# clock_divider.net
KiCad netlist of a schematic drawn in EAGLE
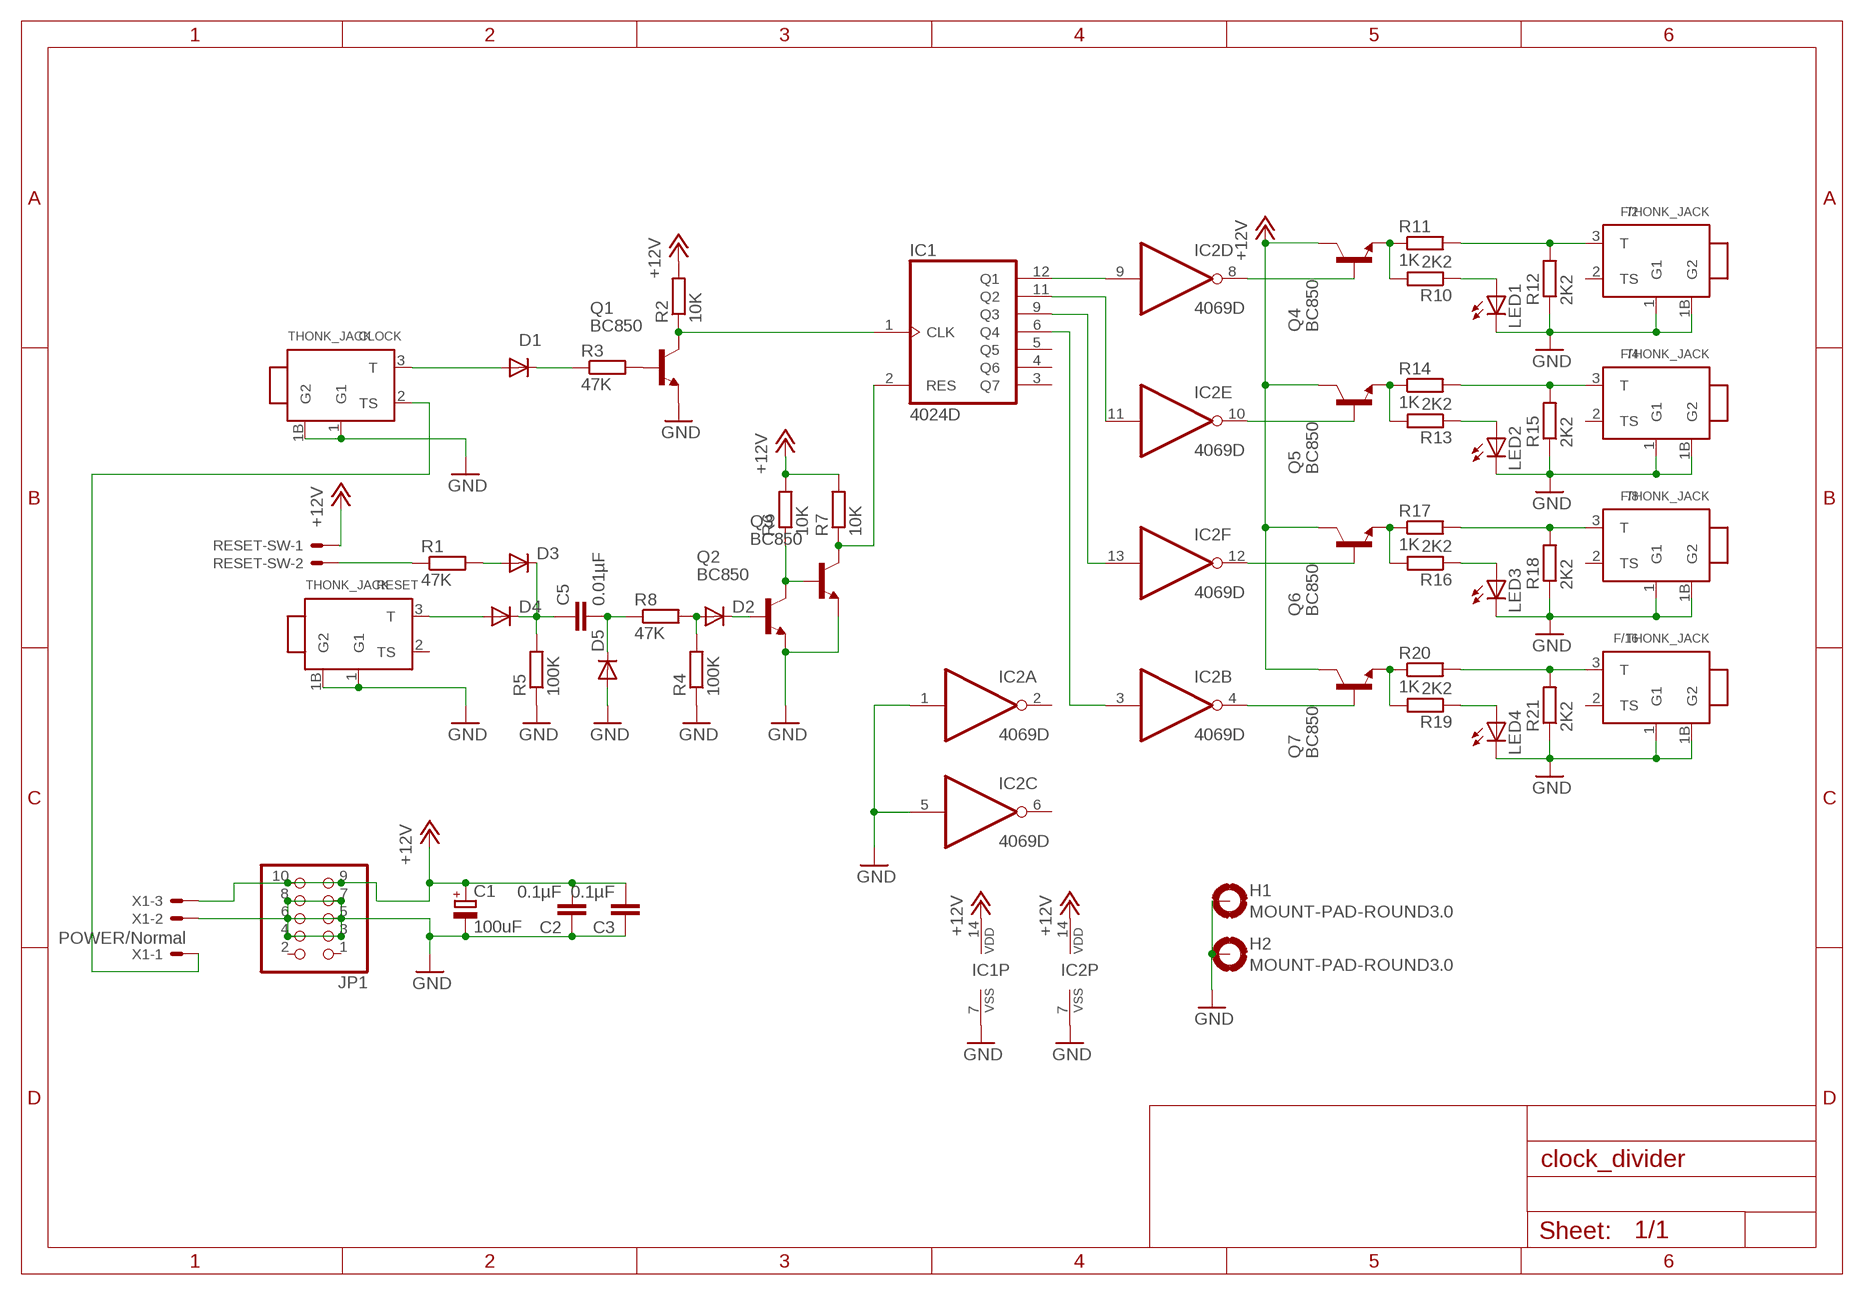
[diagram p0: schematic, sheet 1]

(export (version "E")
  (design (tool "Eeschema 10.0.6"))
  (components
    (comp (ref "C1")
      (value "100uF")
      (footprint "eagle-import:E2,5-6E")
      (libsource (lib "eagle-import") (part "CPOL-EUE2,5-6E"))
    )
    (comp (ref "C2")
      (value "0.1µF")
      (footprint "eagle-import:C0805")
      (libsource (lib "eagle-import") (part "C-EUC0805"))
    )
    (comp (ref "C3")
      (value "0.1µF")
      (footprint "eagle-import:C0805")
      (libsource (lib "eagle-import") (part "C-EUC0805"))
    )
    (comp (ref "C5")
      (value "0.01µF")
      (footprint "eagle-import:C0805")
      (libsource (lib "eagle-import") (part "C-EUC0805"))
    )
    (comp (ref "CLOCK")
      (value "THONK_JACK")
      (footprint "eagle-import:THONK_JACK_P")
      (libsource (lib "eagle-import") (part "THONK_JACK"))
    )
    (comp (ref "D1")
      (value "1N4148")
      (footprint "eagle-import:DO35-7")
      (libsource (lib "eagle-import") (part "1N4148DO35-7"))
    )
    (comp (ref "D2")
      (value "1N4148")
      (footprint "eagle-import:DO35-7")
      (libsource (lib "eagle-import") (part "1N4148DO35-7"))
    )
    (comp (ref "D3")
      (value "1N4148")
      (footprint "eagle-import:DO35-7")
      (libsource (lib "eagle-import") (part "1N4148DO35-7"))
    )
    (comp (ref "D4")
      (value "1N4148")
      (footprint "eagle-import:DO35-7")
      (libsource (lib "eagle-import") (part "1N4148DO35-7"))
    )
    (comp (ref "D5")
      (value "1N4148")
      (footprint "eagle-import:DO35-7")
      (libsource (lib "eagle-import") (part "1N4148DO35-7"))
    )
    (comp (ref "F/2")
      (value "THONK_JACK")
      (footprint "eagle-import:THONK_JACK_P")
      (libsource (lib "eagle-import") (part "THONK_JACK"))
    )
    (comp (ref "F/4")
      (value "THONK_JACK")
      (footprint "eagle-import:THONK_JACK_P")
      (libsource (lib "eagle-import") (part "THONK_JACK"))
    )
    (comp (ref "F/8")
      (value "THONK_JACK")
      (footprint "eagle-import:THONK_JACK_P")
      (libsource (lib "eagle-import") (part "THONK_JACK"))
    )
    (comp (ref "F/16")
      (value "THONK_JACK")
      (footprint "eagle-import:THONK_JACK_P")
      (libsource (lib "eagle-import") (part "THONK_JACK"))
    )
    (comp (ref "H1")
      (value "MOUNT-PAD-ROUND3.0")
      (footprint "eagle-import:3,0-PAD")
      (libsource (lib "eagle-import") (part "MOUNT-PAD-ROUND3.0"))
    )
    (comp (ref "H2")
      (value "MOUNT-PAD-ROUND3.0")
      (footprint "eagle-import:3,0-PAD")
      (libsource (lib "eagle-import") (part "MOUNT-PAD-ROUND3.0"))
    )
    (comp (ref "IC1")
      (value "4024D")
      (footprint "eagle-import:SO14")
      (libsource (lib "eagle-import") (part "4024D"))
    )
    (comp (ref "IC2")
      (value "4069D")
      (footprint "eagle-import:SO14")
      (libsource (lib "eagle-import") (part "4069D"))
    )
    (comp (ref "JP1")
      (value "PINHD-2X5")
      (footprint "eagle-import:2X05")
      (libsource (lib "eagle-import") (part "PINHD-2X5"))
    )
    (comp (ref "LED1")
      (value "LED5MM")
      (footprint "eagle-import:LED5MM")
      (libsource (lib "eagle-import") (part "LED5MM"))
    )
    (comp (ref "LED2")
      (value "LED5MM")
      (footprint "eagle-import:LED5MM")
      (libsource (lib "eagle-import") (part "LED5MM"))
    )
    (comp (ref "LED3")
      (value "LED5MM")
      (footprint "eagle-import:LED5MM")
      (libsource (lib "eagle-import") (part "LED5MM"))
    )
    (comp (ref "LED4")
      (value "LED5MM")
      (footprint "eagle-import:LED5MM")
      (libsource (lib "eagle-import") (part "LED5MM"))
    )
    (comp (ref "Q1")
      (value "BC850")
      (footprint "eagle-import:SOT23")
      (libsource (lib "eagle-import") (part "BC850"))
    )
    (comp (ref "Q2")
      (value "BC850")
      (footprint "eagle-import:SOT23")
      (libsource (lib "eagle-import") (part "BC850"))
    )
    (comp (ref "Q3")
      (value "BC850")
      (footprint "eagle-import:SOT23")
      (libsource (lib "eagle-import") (part "BC850"))
    )
    (comp (ref "Q4")
      (value "BC850")
      (footprint "eagle-import:SOT23")
      (libsource (lib "eagle-import") (part "BC850"))
    )
    (comp (ref "Q5")
      (value "BC850")
      (footprint "eagle-import:SOT23")
      (libsource (lib "eagle-import") (part "BC850"))
    )
    (comp (ref "Q6")
      (value "BC850")
      (footprint "eagle-import:SOT23")
      (libsource (lib "eagle-import") (part "BC850"))
    )
    (comp (ref "Q7")
      (value "BC850")
      (footprint "eagle-import:SOT23")
      (libsource (lib "eagle-import") (part "BC850"))
    )
    (comp (ref "R1")
      (value "47K")
      (footprint "eagle-import:M0805")
      (libsource (lib "eagle-import") (part "R-EU_M0805"))
    )
    (comp (ref "R2")
      (value "10K")
      (footprint "eagle-import:M0805")
      (libsource (lib "eagle-import") (part "R-EU_M0805"))
    )
    (comp (ref "R3")
      (value "47K")
      (footprint "eagle-import:M0805")
      (libsource (lib "eagle-import") (part "R-EU_M0805"))
    )
    (comp (ref "R4")
      (value "100K")
      (footprint "eagle-import:M0805")
      (libsource (lib "eagle-import") (part "R-EU_M0805"))
    )
    (comp (ref "R5")
      (value "100K")
      (footprint "eagle-import:M0805")
      (libsource (lib "eagle-import") (part "R-EU_M0805"))
    )
    (comp (ref "R6")
      (value "10K")
      (footprint "eagle-import:M0805")
      (libsource (lib "eagle-import") (part "R-EU_M0805"))
    )
    (comp (ref "R7")
      (value "10K")
      (footprint "eagle-import:M0805")
      (libsource (lib "eagle-import") (part "R-EU_M0805"))
    )
    (comp (ref "R8")
      (value "47K")
      (footprint "eagle-import:M0805")
      (libsource (lib "eagle-import") (part "R-EU_M0805"))
    )
    (comp (ref "R10")
      (value "2K2")
      (footprint "eagle-import:M0805")
      (libsource (lib "eagle-import") (part "R-EU_M0805"))
    )
    (comp (ref "R11")
      (value "1K")
      (footprint "eagle-import:M0805")
      (libsource (lib "eagle-import") (part "R-EU_M0805"))
    )
    (comp (ref "R12")
      (value "2K2")
      (footprint "eagle-import:M0805")
      (libsource (lib "eagle-import") (part "R-EU_M0805"))
    )
    (comp (ref "R13")
      (value "2K2")
      (footprint "eagle-import:M0805")
      (libsource (lib "eagle-import") (part "R-EU_M0805"))
    )
    (comp (ref "R14")
      (value "1K")
      (footprint "eagle-import:M0805")
      (libsource (lib "eagle-import") (part "R-EU_M0805"))
    )
    (comp (ref "R15")
      (value "2K2")
      (footprint "eagle-import:M0805")
      (libsource (lib "eagle-import") (part "R-EU_M0805"))
    )
    (comp (ref "R16")
      (value "2K2")
      (footprint "eagle-import:M0805")
      (libsource (lib "eagle-import") (part "R-EU_M0805"))
    )
    (comp (ref "R17")
      (value "1K")
      (footprint "eagle-import:M0805")
      (libsource (lib "eagle-import") (part "R-EU_M0805"))
    )
    (comp (ref "R18")
      (value "2K2")
      (footprint "eagle-import:M0805")
      (libsource (lib "eagle-import") (part "R-EU_M0805"))
    )
    (comp (ref "R19")
      (value "2K2")
      (footprint "eagle-import:M0805")
      (libsource (lib "eagle-import") (part "R-EU_M0805"))
    )
    (comp (ref "R20")
      (value "1K")
      (footprint "eagle-import:M0805")
      (libsource (lib "eagle-import") (part "R-EU_M0805"))
    )
    (comp (ref "R21")
      (value "2K2")
      (footprint "eagle-import:M0805")
      (libsource (lib "eagle-import") (part "R-EU_M0805"))
    )
    (comp (ref "RESET")
      (value "THONK_JACK")
      (footprint "eagle-import:THONK_JACK_P")
      (libsource (lib "eagle-import") (part "THONK_JACK"))
    )
    (comp (ref "RESET-SW")
      (value "KK-156-2")
      (footprint "eagle-import:KK-156-2")
      (libsource (lib "eagle-import") (part "KK-156-2"))
    )
    (comp (ref "X1")
      (value "POWER/Normal")
      (footprint "eagle-import:KK-156-3")
      (libsource (lib "eagle-import") (part "KK-156-3"))
    )
  )
  (nets
    (net (code "1") (name "+12V") (class "Default")
      (node (ref "C1") (pin "+") (pinfunction "+_+") (pintype "passive"))
      (node (ref "C2") (pin "2") (pinfunction "2_2") (pintype "passive"))
      (node (ref "C3") (pin "2") (pinfunction "2_2") (pintype "passive"))
      (node (ref "IC1") (pin "14") (pinfunction "VDD_14") (pintype "power_in"))
      (node (ref "IC2") (pin "14") (pinfunction "VDD_14") (pintype "power_in"))
      (node (ref "JP1") (pin "10") (pinfunction "10_10") (pintype "passive"))
      (node (ref "JP1") (pin "9") (pinfunction "9_9") (pintype "passive"))
      (node (ref "Q4") (pin "3") (pinfunction "C_3") (pintype "passive"))
      (node (ref "Q5") (pin "3") (pinfunction "C_3") (pintype "passive"))
      (node (ref "Q6") (pin "3") (pinfunction "C_3") (pintype "passive"))
      (node (ref "Q7") (pin "3") (pinfunction "C_3") (pintype "passive"))
      (node (ref "R2") (pin "2") (pinfunction "2_2") (pintype "passive"))
      (node (ref "R6") (pin "2") (pinfunction "2_2") (pintype "passive"))
      (node (ref "R7") (pin "2") (pinfunction "2_2") (pintype "passive"))
      (node (ref "RESET-SW") (pin "1") (pinfunction "S_1") (pintype "passive"))
      (node (ref "X1") (pin "3") (pinfunction "S_3") (pintype "passive"))
    )
    (net (code "2") (name "GND") (class "Default")
      (node (ref "C1") (pin "-") (pinfunction "-_-") (pintype "passive"))
      (node (ref "C2") (pin "1") (pinfunction "1_1") (pintype "passive"))
      (node (ref "C3") (pin "1") (pinfunction "1_1") (pintype "passive"))
      (node (ref "CLOCK") (pin "1") (pinfunction "G1_1") (pintype "bidirectional"))
      (node (ref "CLOCK") (pin "1B") (pinfunction "G2_1B") (pintype "bidirectional"))
      (node (ref "D5") (pin "A") (pinfunction "A_A") (pintype "passive"))
      (node (ref "F/16") (pin "1") (pinfunction "G1_1") (pintype "bidirectional"))
      (node (ref "F/16") (pin "1B") (pinfunction "G2_1B") (pintype "bidirectional"))
      (node (ref "F/2") (pin "1") (pinfunction "G1_1") (pintype "bidirectional"))
      (node (ref "F/2") (pin "1B") (pinfunction "G2_1B") (pintype "bidirectional"))
      (node (ref "F/4") (pin "1") (pinfunction "G1_1") (pintype "bidirectional"))
      (node (ref "F/4") (pin "1B") (pinfunction "G2_1B") (pintype "bidirectional"))
      (node (ref "F/8") (pin "1") (pinfunction "G1_1") (pintype "bidirectional"))
      (node (ref "F/8") (pin "1B") (pinfunction "G2_1B") (pintype "bidirectional"))
      (node (ref "H1") (pin "B3,0") (pinfunction "MOUNT_B3,0") (pintype "passive"))
      (node (ref "H2") (pin "B3,0") (pinfunction "MOUNT_B3,0") (pintype "passive"))
      (node (ref "IC1") (pin "7") (pinfunction "VSS_7") (pintype "power_in"))
      (node (ref "IC2") (pin "1") (pinfunction "I_1") (pintype "input"))
      (node (ref "IC2") (pin "5") (pinfunction "I_5") (pintype "input"))
      (node (ref "IC2") (pin "7") (pinfunction "VSS_7") (pintype "power_in"))
      (node (ref "JP1") (pin "3") (pinfunction "3_3") (pintype "passive"))
      (node (ref "JP1") (pin "4") (pinfunction "4_4") (pintype "passive"))
      (node (ref "JP1") (pin "5") (pinfunction "5_5") (pintype "passive"))
      (node (ref "JP1") (pin "6") (pinfunction "6_6") (pintype "passive"))
      (node (ref "JP1") (pin "7") (pinfunction "7_7") (pintype "passive"))
      (node (ref "JP1") (pin "8") (pinfunction "8_8") (pintype "passive"))
      (node (ref "LED1") (pin "K") (pinfunction "C_K") (pintype "passive"))
      (node (ref "LED2") (pin "K") (pinfunction "C_K") (pintype "passive"))
      (node (ref "LED3") (pin "K") (pinfunction "C_K") (pintype "passive"))
      (node (ref "LED4") (pin "K") (pinfunction "C_K") (pintype "passive"))
      (node (ref "Q1") (pin "2") (pinfunction "E_2") (pintype "passive"))
      (node (ref "Q2") (pin "2") (pinfunction "E_2") (pintype "passive"))
      (node (ref "Q3") (pin "2") (pinfunction "E_2") (pintype "passive"))
      (node (ref "R12") (pin "1") (pinfunction "1_1") (pintype "passive"))
      (node (ref "R15") (pin "1") (pinfunction "1_1") (pintype "passive"))
      (node (ref "R18") (pin "1") (pinfunction "1_1") (pintype "passive"))
      (node (ref "R21") (pin "1") (pinfunction "1_1") (pintype "passive"))
      (node (ref "R4") (pin "1") (pinfunction "1_1") (pintype "passive"))
      (node (ref "R5") (pin "1") (pinfunction "1_1") (pintype "passive"))
      (node (ref "RESET") (pin "1") (pinfunction "G1_1") (pintype "bidirectional"))
      (node (ref "RESET") (pin "1B") (pinfunction "G2_1B") (pintype "bidirectional"))
      (node (ref "X1") (pin "2") (pinfunction "S_2") (pintype "passive"))
    )
    (net (code "3") (name "Net-(C5-Pad1)") (class "Default")
      (node (ref "C5") (pin "1") (pinfunction "1_1") (pintype "passive"))
      (node (ref "D3") (pin "C") (pinfunction "C_C") (pintype "passive"))
      (node (ref "D4") (pin "C") (pinfunction "C_C") (pintype "passive"))
      (node (ref "R5") (pin "2") (pinfunction "2_2") (pintype "passive"))
    )
    (net (code "4") (name "Net-(C5-Pad2)") (class "Default")
      (node (ref "C5") (pin "2") (pinfunction "2_2") (pintype "passive"))
      (node (ref "D5") (pin "C") (pinfunction "C_C") (pintype "passive"))
      (node (ref "R8") (pin "1") (pinfunction "1_1") (pintype "passive"))
    )
    (net (code "5") (name "Net-(CLOCK-T)") (class "Default")
      (node (ref "CLOCK") (pin "3") (pinfunction "T_3") (pintype "bidirectional"))
      (node (ref "D1") (pin "A") (pinfunction "A_A") (pintype "passive"))
    )
    (net (code "6") (name "Net-(CLOCK-TS)") (class "Default")
      (node (ref "CLOCK") (pin "2") (pinfunction "TS_2") (pintype "bidirectional"))
      (node (ref "X1") (pin "1") (pinfunction "S_1") (pintype "passive"))
    )
    (net (code "7") (name "Net-(D1-PadC)") (class "Default")
      (node (ref "D1") (pin "C") (pinfunction "C_C") (pintype "passive"))
      (node (ref "R3") (pin "1") (pinfunction "1_1") (pintype "passive"))
    )
    (net (code "8") (name "Net-(D2-PadA)") (class "Default")
      (node (ref "D2") (pin "A") (pinfunction "A_A") (pintype "passive"))
      (node (ref "R4") (pin "2") (pinfunction "2_2") (pintype "passive"))
      (node (ref "R8") (pin "2") (pinfunction "2_2") (pintype "passive"))
    )
    (net (code "9") (name "Net-(D3-PadA)") (class "Default")
      (node (ref "D3") (pin "A") (pinfunction "A_A") (pintype "passive"))
      (node (ref "R1") (pin "2") (pinfunction "2_2") (pintype "passive"))
    )
    (net (code "10") (name "Net-(F/2-T)") (class "Default")
      (node (ref "F/2") (pin "3") (pinfunction "T_3") (pintype "bidirectional"))
      (node (ref "R11") (pin "2") (pinfunction "2_2") (pintype "passive"))
      (node (ref "R12") (pin "2") (pinfunction "2_2") (pintype "passive"))
    )
    (net (code "11") (name "Net-(F/4-T)") (class "Default")
      (node (ref "F/4") (pin "3") (pinfunction "T_3") (pintype "bidirectional"))
      (node (ref "R14") (pin "2") (pinfunction "2_2") (pintype "passive"))
      (node (ref "R15") (pin "2") (pinfunction "2_2") (pintype "passive"))
    )
    (net (code "12") (name "Net-(F/8-T)") (class "Default")
      (node (ref "F/8") (pin "3") (pinfunction "T_3") (pintype "bidirectional"))
      (node (ref "R17") (pin "2") (pinfunction "2_2") (pintype "passive"))
      (node (ref "R18") (pin "2") (pinfunction "2_2") (pintype "passive"))
    )
    (net (code "13") (name "Net-(F/16-T)") (class "Default")
      (node (ref "F/16") (pin "3") (pinfunction "T_3") (pintype "bidirectional"))
      (node (ref "R20") (pin "2") (pinfunction "2_2") (pintype "passive"))
      (node (ref "R21") (pin "2") (pinfunction "2_2") (pintype "passive"))
    )
    (net (code "14") (name "Net-(IC1A-CLK)") (class "Default")
      (node (ref "IC1") (pin "1") (pinfunction "CLK_1") (pintype "input"))
      (node (ref "Q1") (pin "3") (pinfunction "C_3") (pintype "passive"))
      (node (ref "R2") (pin "1") (pinfunction "1_1") (pintype "passive"))
    )
    (net (code "15") (name "Net-(IC1A-Q1)") (class "Default")
      (node (ref "IC1") (pin "12") (pinfunction "Q1_12") (pintype "output"))
      (node (ref "IC2") (pin "9") (pinfunction "I_9") (pintype "input"))
    )
    (net (code "16") (name "Net-(IC1A-Q2)") (class "Default")
      (node (ref "IC1") (pin "11") (pinfunction "Q2_11") (pintype "output"))
      (node (ref "IC2") (pin "11") (pinfunction "I_11") (pintype "input"))
    )
    (net (code "17") (name "Net-(IC1A-Q3)") (class "Default")
      (node (ref "IC1") (pin "9") (pinfunction "Q3_9") (pintype "output"))
      (node (ref "IC2") (pin "13") (pinfunction "I_13") (pintype "input"))
    )
    (net (code "18") (name "Net-(IC1A-Q4)") (class "Default")
      (node (ref "IC1") (pin "6") (pinfunction "Q4_6") (pintype "output"))
      (node (ref "IC2") (pin "3") (pinfunction "I_3") (pintype "input"))
    )
    (net (code "19") (name "Net-(IC1A-RES)") (class "Default")
      (node (ref "IC1") (pin "2") (pinfunction "RES_2") (pintype "input"))
      (node (ref "Q3") (pin "3") (pinfunction "C_3") (pintype "passive"))
      (node (ref "R7") (pin "1") (pinfunction "1_1") (pintype "passive"))
    )
    (net (code "20") (name "Net-(IC2B-O)") (class "Default")
      (node (ref "IC2") (pin "4") (pinfunction "O_4") (pintype "output"))
      (node (ref "Q7") (pin "1") (pinfunction "B_1") (pintype "passive"))
    )
    (net (code "21") (name "Net-(IC2D-O)") (class "Default")
      (node (ref "IC2") (pin "8") (pinfunction "O_8") (pintype "output"))
      (node (ref "Q4") (pin "1") (pinfunction "B_1") (pintype "passive"))
    )
    (net (code "22") (name "Net-(IC2E-O)") (class "Default")
      (node (ref "IC2") (pin "10") (pinfunction "O_10") (pintype "output"))
      (node (ref "Q5") (pin "1") (pinfunction "B_1") (pintype "passive"))
    )
    (net (code "23") (name "Net-(IC2F-O)") (class "Default")
      (node (ref "IC2") (pin "12") (pinfunction "O_12") (pintype "output"))
      (node (ref "Q6") (pin "1") (pinfunction "B_1") (pintype "passive"))
    )
    (net (code "24") (name "Net-(LED1-PadA)") (class "Default")
      (node (ref "LED1") (pin "A") (pinfunction "A_A") (pintype "passive"))
      (node (ref "R10") (pin "1") (pinfunction "1_1") (pintype "passive"))
    )
    (net (code "25") (name "Net-(LED2-PadA)") (class "Default")
      (node (ref "LED2") (pin "A") (pinfunction "A_A") (pintype "passive"))
      (node (ref "R13") (pin "1") (pinfunction "1_1") (pintype "passive"))
    )
    (net (code "26") (name "Net-(LED3-PadA)") (class "Default")
      (node (ref "LED3") (pin "A") (pinfunction "A_A") (pintype "passive"))
      (node (ref "R16") (pin "1") (pinfunction "1_1") (pintype "passive"))
    )
    (net (code "27") (name "Net-(LED4-PadA)") (class "Default")
      (node (ref "LED4") (pin "A") (pinfunction "A_A") (pintype "passive"))
      (node (ref "R19") (pin "1") (pinfunction "1_1") (pintype "passive"))
    )
    (net (code "28") (name "Net-(Q1-B)") (class "Default")
      (node (ref "Q1") (pin "1") (pinfunction "B_1") (pintype "passive"))
      (node (ref "R3") (pin "2") (pinfunction "2_2") (pintype "passive"))
    )
    (net (code "29") (name "Net-(Q2-B)") (class "Default")
      (node (ref "D2") (pin "C") (pinfunction "C_C") (pintype "passive"))
      (node (ref "Q2") (pin "1") (pinfunction "B_1") (pintype "passive"))
    )
    (net (code "30") (name "Net-(Q2-C)") (class "Default")
      (node (ref "Q2") (pin "3") (pinfunction "C_3") (pintype "passive"))
      (node (ref "Q3") (pin "1") (pinfunction "B_1") (pintype "passive"))
      (node (ref "R6") (pin "1") (pinfunction "1_1") (pintype "passive"))
    )
    (net (code "31") (name "Net-(Q4-E)") (class "Default")
      (node (ref "Q4") (pin "2") (pinfunction "E_2") (pintype "passive"))
      (node (ref "R10") (pin "2") (pinfunction "2_2") (pintype "passive"))
      (node (ref "R11") (pin "1") (pinfunction "1_1") (pintype "passive"))
    )
    (net (code "32") (name "Net-(Q5-E)") (class "Default")
      (node (ref "Q5") (pin "2") (pinfunction "E_2") (pintype "passive"))
      (node (ref "R13") (pin "2") (pinfunction "2_2") (pintype "passive"))
      (node (ref "R14") (pin "1") (pinfunction "1_1") (pintype "passive"))
    )
    (net (code "33") (name "Net-(Q6-E)") (class "Default")
      (node (ref "Q6") (pin "2") (pinfunction "E_2") (pintype "passive"))
      (node (ref "R16") (pin "2") (pinfunction "2_2") (pintype "passive"))
      (node (ref "R17") (pin "1") (pinfunction "1_1") (pintype "passive"))
    )
    (net (code "34") (name "Net-(Q7-E)") (class "Default")
      (node (ref "Q7") (pin "2") (pinfunction "E_2") (pintype "passive"))
      (node (ref "R19") (pin "2") (pinfunction "2_2") (pintype "passive"))
      (node (ref "R20") (pin "1") (pinfunction "1_1") (pintype "passive"))
    )
    (net (code "35") (name "Net-(RESET-SWB-S)") (class "Default")
      (node (ref "R1") (pin "1") (pinfunction "1_1") (pintype "passive"))
      (node (ref "RESET-SW") (pin "2") (pinfunction "S_2") (pintype "passive"))
    )
    (net (code "36") (name "Net-(RESET-T)") (class "Default")
      (node (ref "D4") (pin "A") (pinfunction "A_A") (pintype "passive"))
      (node (ref "RESET") (pin "3") (pinfunction "T_3") (pintype "bidirectional"))
    )
    (net (code "37") (name "unconnected-(F/2-TS-Pad2)") (class "Default")
      (node (ref "F/2") (pin "2") (pinfunction "TS_2") (pintype "bidirectional"))
    )
    (net (code "38") (name "unconnected-(F/4-TS-Pad2)") (class "Default")
      (node (ref "F/4") (pin "2") (pinfunction "TS_2") (pintype "bidirectional"))
    )
    (net (code "39") (name "unconnected-(F/8-TS-Pad2)") (class "Default")
      (node (ref "F/8") (pin "2") (pinfunction "TS_2") (pintype "bidirectional"))
    )
    (net (code "40") (name "unconnected-(F/16-TS-Pad2)") (class "Default")
      (node (ref "F/16") (pin "2") (pinfunction "TS_2") (pintype "bidirectional"))
    )
    (net (code "41") (name "unconnected-(IC1A-Q5-Pad5)") (class "Default")
      (node (ref "IC1") (pin "5") (pinfunction "Q5_5") (pintype "output"))
    )
    (net (code "42") (name "unconnected-(IC1A-Q6-Pad4)") (class "Default")
      (node (ref "IC1") (pin "4") (pinfunction "Q6_4") (pintype "output"))
    )
    (net (code "43") (name "unconnected-(IC1A-Q7-Pad3)") (class "Default")
      (node (ref "IC1") (pin "3") (pinfunction "Q7_3") (pintype "output"))
    )
    (net (code "44") (name "unconnected-(IC2A-O-Pad2)") (class "Default")
      (node (ref "IC2") (pin "2") (pinfunction "O_2") (pintype "output"))
    )
    (net (code "45") (name "unconnected-(IC2C-O-Pad6)") (class "Default")
      (node (ref "IC2") (pin "6") (pinfunction "O_6") (pintype "output"))
    )
    (net (code "46") (name "unconnected-(JP1-Pad1)") (class "Default")
      (node (ref "JP1") (pin "1") (pinfunction "1_1") (pintype "passive"))
    )
    (net (code "47") (name "unconnected-(JP1-Pad2)") (class "Default")
      (node (ref "JP1") (pin "2") (pinfunction "2_2") (pintype "passive"))
    )
    (net (code "48") (name "unconnected-(RESET-TS-Pad2)") (class "Default")
      (node (ref "RESET") (pin "2") (pinfunction "TS_2") (pintype "bidirectional"))
    )
  )
)
